# heart.net
KiCad netlist of a schematic drawn in EAGLE
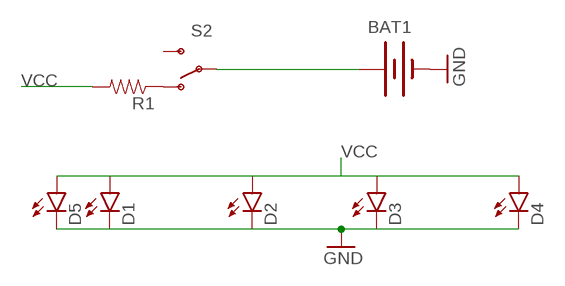
[diagram p0: schematic, sheet 1]

(export (version "E")
  (design (tool "Eeschema 10.0.6"))
  (components
    (comp (ref "BAT1")
      (value "BATTERY12MM")
      (footprint "eagle-import:BATTCON_12MM")
      (libsource (lib "eagle-import") (part "BATTERY12MM"))
    )
    (comp (ref "D1")
      (value "LED0603")
      (footprint "eagle-import:LED-0603")
      (libsource (lib "eagle-import") (part "LED0603"))
    )
    (comp (ref "D2")
      (value "LED0603")
      (footprint "eagle-import:LED-0603")
      (libsource (lib "eagle-import") (part "LED0603"))
    )
    (comp (ref "D3")
      (value "LED0603")
      (footprint "eagle-import:LED-0603")
      (libsource (lib "eagle-import") (part "LED0603"))
    )
    (comp (ref "D4")
      (value "LED0603")
      (footprint "eagle-import:LED-0603")
      (libsource (lib "eagle-import") (part "LED0603"))
    )
    (comp (ref "D5")
      (value "LED0603")
      (footprint "eagle-import:LED-0603")
      (libsource (lib "eagle-import") (part "LED0603"))
    )
    (comp (ref "R1")
      (value "RESISTOR0603")
      (footprint "eagle-import:0603-RES")
      (libsource (lib "eagle-import") (part "RESISTOR0603"))
    )
    (comp (ref "S2")
      (value "SWITCH-SPDTSMD_NOHOLE")
      (footprint "eagle-import:AYZ0202_NOHOLE")
      (libsource (lib "eagle-import") (part "SWITCH-SPDTSMD_NOHOLE"))
    )
  )
  (nets
    (net (code "1") (name "/VCC") (class "Default")
      (node (ref "D1") (pin "A") (pinfunction "A_A") (pintype "passive"))
      (node (ref "D2") (pin "A") (pinfunction "A_A") (pintype "passive"))
      (node (ref "D3") (pin "A") (pinfunction "A_A") (pintype "passive"))
      (node (ref "D4") (pin "A") (pinfunction "A_A") (pintype "passive"))
      (node (ref "D5") (pin "A") (pinfunction "A_A") (pintype "passive"))
      (node (ref "R1") (pin "2") (pinfunction "2_2") (pintype "passive"))
    )
    (net (code "2") (name "GND") (class "Default")
      (node (ref "BAT1") (pin "GND") (pinfunction "-_GND") (pintype "power_in"))
      (node (ref "D1") (pin "C") (pinfunction "C_C") (pintype "passive"))
      (node (ref "D2") (pin "C") (pinfunction "C_C") (pintype "passive"))
      (node (ref "D3") (pin "C") (pinfunction "C_C") (pintype "passive"))
      (node (ref "D4") (pin "C") (pinfunction "C_C") (pintype "passive"))
      (node (ref "D5") (pin "C") (pinfunction "C_C") (pintype "passive"))
    )
    (net (code "3") (name "Net-(BAT1-+)") (class "Default")
      (node (ref "BAT1") (pin "PWR@1") (pinfunction "+_PWR@1") (pintype "power_in"))
      (node (ref "S2") (pin "2") (pinfunction "P_2") (pintype "passive"))
    )
    (net (code "4") (name "Net-(S2-O)") (class "Default")
      (node (ref "R1") (pin "1") (pinfunction "1_1") (pintype "passive"))
      (node (ref "S2") (pin "1") (pinfunction "O_1") (pintype "passive"))
    )
    (net (code "5") (name "unconnected-(S2-S-Pad3)") (class "Default")
      (node (ref "S2") (pin "3") (pinfunction "S_3") (pintype "passive"))
    )
  )
)
